# ProDoc_TwinWave_2026-01-06.net
KiCad netlist of a schematic drawn in EasyEDA Pro
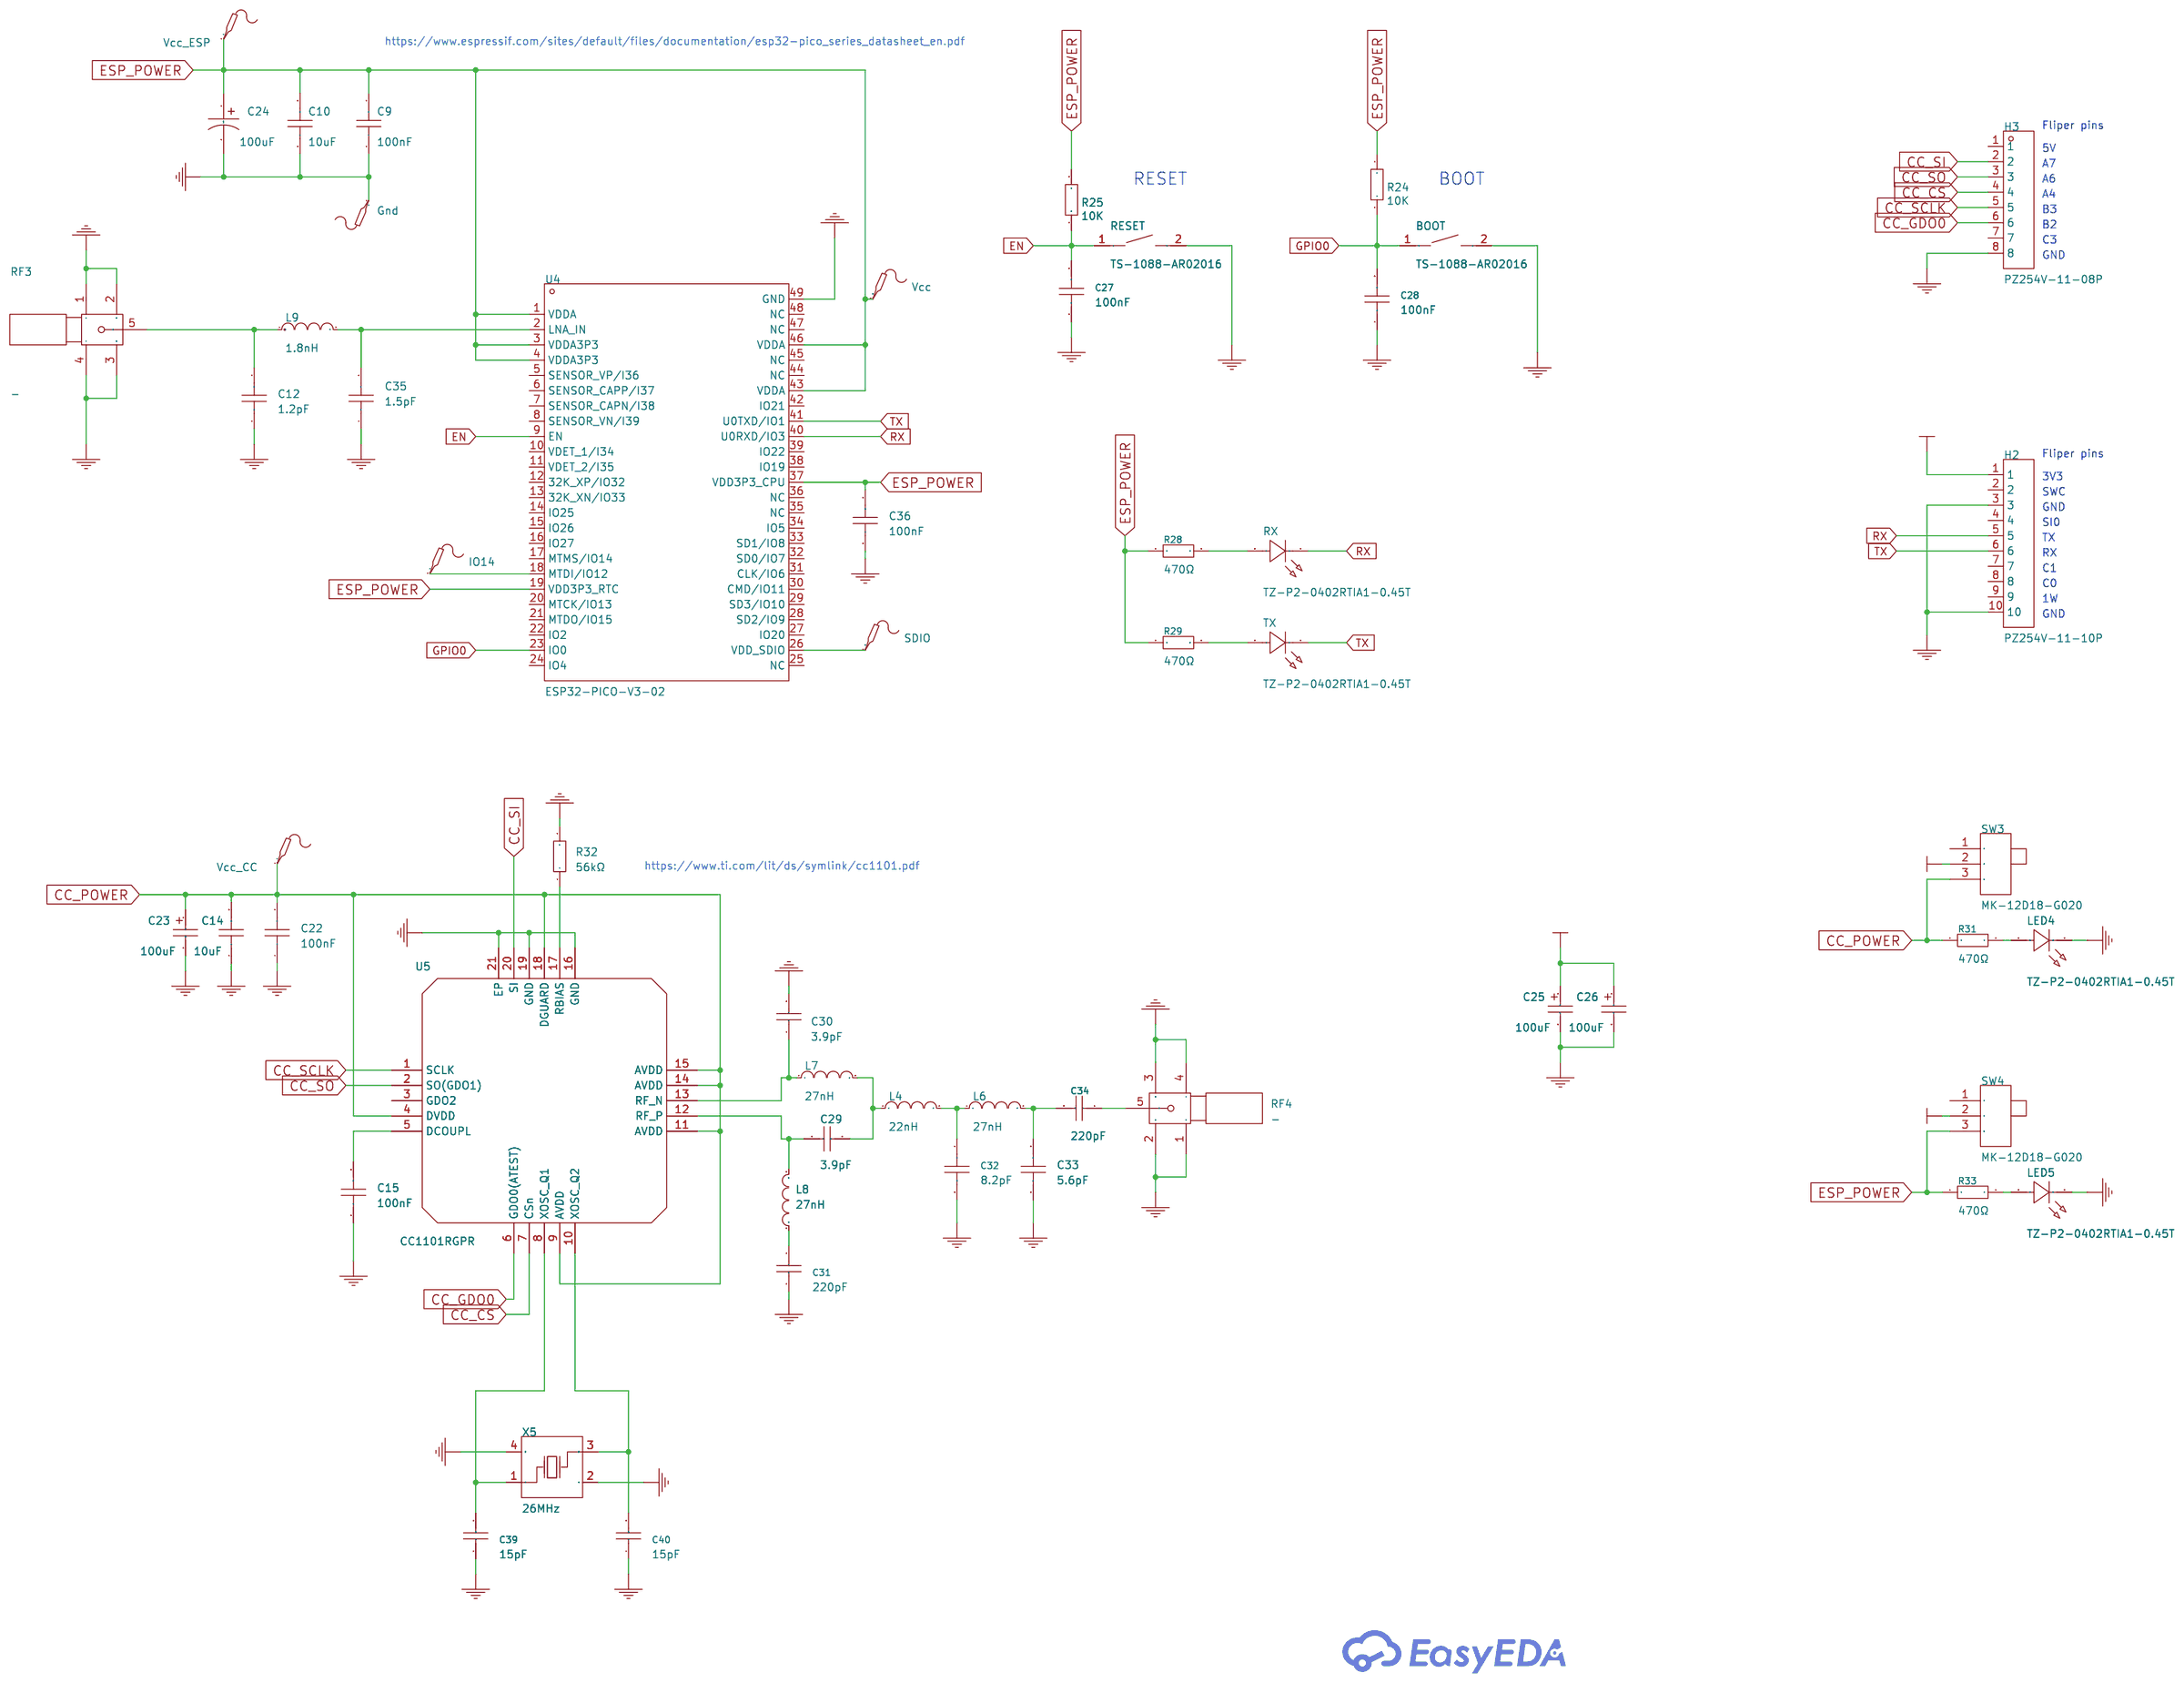
[diagram p0: schematic sheet]

(export (version "E")
  (design (tool "Eeschema 10.0.6"))
  (components
    (comp (ref "BOOT")
      (value "TS-1088-AR02016")
      (footprint "easyedapro:SW-SMD_L3.9-W3.0-P4.45")
      (fields (field (name "Manufacturer") "XUNPU(讯普)"))
      (libsource (lib "easyedapro") (part "TS-1088-AR02016"))
    )
    (comp (ref "C9")
      (value "100nF")
      (footprint "easyedapro:C0603")
      (description "Capacitance:100nF Tolerance:±10% Tolerance:±10% Voltage Rating:50V Temperature Coefficient:X7R")
      (fields
        (field (name "Manufacturer Part") "CC0603KRX7R9BB104")
        (field (name "Manufacturer") "YAGEO(国巨)")
      )
      (libsource (lib "easyedapro") (part "CC0603KRX7R9BB104"))
    )
    (comp (ref "C10")
      (value "10uF")
      (footprint "easyedapro:C0603")
      (fields
        (field (name "Manufacturer Part") "CL10A106MP8NNNC")
        (field (name "Manufacturer") "SAMSUNG(三星)")
      )
      (libsource (lib "easyedapro") (part "CL10A106MP8NNNC"))
    )
    (comp (ref "C12")
      (value "1.2pF")
      (footprint "easyedapro:C0201")
      (fields
        (field (name "Manufacturer Part") "GRM0335C1H1R2BA01D")
        (field (name "Manufacturer") "muRata(村田)")
      )
      (libsource (lib "easyedapro") (part "GRM0335C1H1R2BA01D"))
    )
    (comp (ref "C14")
      (value "10uF")
      (footprint "easyedapro:C0603")
      (fields
        (field (name "Manufacturer Part") "CL10A106MP8NNNC")
        (field (name "Manufacturer") "SAMSUNG(三星)")
      )
      (libsource (lib "easyedapro") (part "CL10A106MP8NNNC"))
    )
    (comp (ref "C15")
      (value "100nF")
      (footprint "easyedapro:C0603")
      (description "Capacitance:100nF Tolerance:±10% Tolerance:±10% Voltage Rating:50V Temperature Coefficient:X7R")
      (fields
        (field (name "Manufacturer Part") "CC0603KRX7R9BB104")
        (field (name "Manufacturer") "YAGEO(国巨)")
      )
      (libsource (lib "easyedapro") (part "CC0603KRX7R9BB104"))
    )
    (comp (ref "C22")
      (value "100nF")
      (footprint "easyedapro:C0603")
      (description "Capacitance:100nF Tolerance:±10% Tolerance:±10% Voltage Rating:50V Temperature Coefficient:X7R")
      (fields
        (field (name "Manufacturer Part") "CC0603KRX7R9BB104")
        (field (name "Manufacturer") "YAGEO(国巨)")
      )
      (libsource (lib "easyedapro") (part "CC0603KRX7R9BB104"))
    )
    (comp (ref "C23")
      (value "100uF")
      (footprint "easyedapro:CASE-B_3528")
      (fields (field (name "Manufacturer Part") "TAJB107K006RNJ") (field (name "Manufacturer") "Kyocera AVX"))
      (libsource (lib "easyedapro") (part "TAJB107K006RNJ"))
    )
    (comp (ref "C24")
      (value "100uF")
      (footprint "easyedapro:CASE-B_3528-1")
      (fields
        (field (name "Manufacturer Part") "TPSB107K006R0250")
        (field (name "Manufacturer") "Kyocera AVX")
      )
      (libsource (lib "easyedapro") (part "TPSB107K006R0250"))
    )
    (comp (ref "C25")
      (value "100uF")
      (footprint "easyedapro:CASE-B_3528")
      (fields (field (name "Manufacturer Part") "TAJB107K006RNJ") (field (name "Manufacturer") "Kyocera AVX"))
      (libsource (lib "easyedapro") (part "TAJB107K006RNJ"))
    )
    (comp (ref "C26")
      (value "100uF")
      (footprint "easyedapro:CASE-B_3528")
      (fields (field (name "Manufacturer Part") "TAJB107K006RNJ") (field (name "Manufacturer") "Kyocera AVX"))
      (libsource (lib "easyedapro") (part "TAJB107K006RNJ"))
    )
    (comp (ref "C27")
      (value "100nF")
      (footprint "easyedapro:C0402")
      (fields
        (field (name "Manufacturer Part") "CC0402KRX7R7BB104")
        (field (name "Manufacturer") "YAGEO(国巨)")
      )
      (libsource (lib "easyedapro") (part "CC0402KRX7R7BB104"))
    )
    (comp (ref "C28")
      (value "100nF")
      (footprint "easyedapro:C0402")
      (fields
        (field (name "Manufacturer Part") "CC0402KRX7R7BB104")
        (field (name "Manufacturer") "YAGEO(国巨)")
      )
      (libsource (lib "easyedapro") (part "CC0402KRX7R7BB104"))
    )
    (comp (ref "C29")
      (value "3.9pF")
      (footprint "easyedapro:C0402")
      (fields (field (name "Manufacturer Part") "0402CG3R9C500NT") (field (name "Manufacturer") "FH(风华)"))
      (libsource (lib "easyedapro") (part "0402CG3R9C500NT"))
    )
    (comp (ref "C30")
      (value "3.9pF")
      (footprint "easyedapro:C0402")
      (fields (field (name "Manufacturer Part") "0402CG3R9C500NT") (field (name "Manufacturer") "FH(风华)"))
      (libsource (lib "easyedapro") (part "0402CG3R9C500NT"))
    )
    (comp (ref "C31")
      (value "220pF")
      (footprint "easyedapro:C0402")
      (description "Capacitance:220pF Tolerance:±5% Tolerance:±5% Voltage Rating:50V Temperature Coefficient:NP0")
      (fields
        (field (name "Manufacturer Part") "CC0402JRNPO9BN221")
        (field (name "Manufacturer") "YAGEO(国巨)")
      )
      (libsource (lib "easyedapro") (part "CC0402JRNPO9BN221"))
    )
    (comp (ref "C32")
      (value "8.2pF")
      (footprint "easyedapro:C0402")
      (fields
        (field (name "Manufacturer Part") "CC0402BRNPO9BN8R2")
        (field (name "Manufacturer") "YAGEO(国巨)")
      )
      (libsource (lib "easyedapro") (part "CC0402BRNPO9BN8R2"))
    )
    (comp (ref "C33")
      (value "5.6pF")
      (footprint "easyedapro:C0402")
      (fields
        (field (name "Manufacturer Part") "CC0402BRNPO9BN5R6")
        (field (name "Manufacturer") "YAGEO(国巨)")
      )
      (libsource (lib "easyedapro") (part "CC0402BRNPO9BN5R6"))
    )
    (comp (ref "C34")
      (value "220pF")
      (footprint "easyedapro:C0402")
      (description "Capacitance:220pF Tolerance:±5% Tolerance:±5% Voltage Rating:50V Temperature Coefficient:NP0")
      (fields
        (field (name "Manufacturer Part") "CC0402JRNPO9BN221")
        (field (name "Manufacturer") "YAGEO(国巨)")
      )
      (libsource (lib "easyedapro") (part "CC0402JRNPO9BN221"))
    )
    (comp (ref "C35")
      (value "1.5pF")
      (footprint "easyedapro:C0201")
      (fields
        (field (name "Manufacturer Part") "GRM0335C1H1R5BA01D")
        (field (name "Manufacturer") "muRata(村田)")
      )
      (libsource (lib "easyedapro") (part "GRM0335C1H1R5BA01D"))
    )
    (comp (ref "C36")
      (value "100nF")
      (footprint "easyedapro:C0603")
      (description "Capacitance:100nF Tolerance:±10% Tolerance:±10% Voltage Rating:50V Temperature Coefficient:X7R")
      (fields
        (field (name "Manufacturer Part") "CC0603KRX7R9BB104")
        (field (name "Manufacturer") "YAGEO(国巨)")
      )
      (libsource (lib "easyedapro") (part "CC0603KRX7R9BB104"))
    )
    (comp (ref "C39")
      (value "15pF")
      (footprint "easyedapro:C0402")
      (fields
        (field (name "Manufacturer Part") "CC0402JRNPO9BN150")
        (field (name "Manufacturer") "YAGEO(国巨)")
      )
      (libsource (lib "easyedapro") (part "CC0402JRNPO9BN150"))
    )
    (comp (ref "C40")
      (value "15pF")
      (footprint "easyedapro:C0402")
      (fields
        (field (name "Manufacturer Part") "CC0402JRNPO9BN150")
        (field (name "Manufacturer") "YAGEO(国巨)")
      )
      (libsource (lib "easyedapro") (part "CC0402JRNPO9BN150"))
    )
    (comp (ref "Gnd")
      (value "~")
      (footprint "easyedapro:Test-Point-0.5mm")
      (description "Test Point 测试点")
      (libsource (lib "easyedapro") (part "Test-Point"))
    )
    (comp (ref "H2")
      (value "PZ254V-11-10P")
      (footprint "easyedapro:HDR-TH_10P-P2.54-V-M")
      (fields (field (name "Manufacturer") "XFCN(兴飞)"))
      (libsource (lib "easyedapro") (part "PZ254V-11-10P"))
    )
    (comp (ref "H3")
      (value "PZ254V-11-08P")
      (footprint "easyedapro:HDR-TH_8P-P2.54-V-M")
      (fields (field (name "Manufacturer") "XFCN(兴飞)"))
      (libsource (lib "easyedapro") (part "PZ254V-11-08P"))
    )
    (comp (ref "IO14")
      (value "~")
      (footprint "easyedapro:Test-Point-0.5mm")
      (description "Test Point 测试点")
      (libsource (lib "easyedapro") (part "Test-Point"))
    )
    (comp (ref "L4")
      (value "22nH")
      (footprint "easyedapro:L0402")
      (fields (field (name "Manufacturer Part") "LQG15HS22NJ02D") (field (name "Manufacturer") "muRata(村田)"))
      (libsource (lib "easyedapro") (part "LQG15HS22NJ02D"))
    )
    (comp (ref "L6")
      (value "27nH")
      (footprint "easyedapro:L0402-RD")
      (fields (field (name "Manufacturer Part") "LQG15HS27NJ02D") (field (name "Manufacturer") "muRata(村田)"))
      (libsource (lib "easyedapro") (part "LQG15HS27NJ02D"))
    )
    (comp (ref "L7")
      (value "27nH")
      (footprint "easyedapro:L0402-RD")
      (fields (field (name "Manufacturer Part") "LQG15HS27NJ02D") (field (name "Manufacturer") "muRata(村田)"))
      (libsource (lib "easyedapro") (part "LQG15HS27NJ02D"))
    )
    (comp (ref "L8")
      (value "27nH")
      (footprint "easyedapro:L0402-RD")
      (fields (field (name "Manufacturer Part") "LQG15HS27NJ02D") (field (name "Manufacturer") "muRata(村田)"))
      (libsource (lib "easyedapro") (part "LQG15HS27NJ02D"))
    )
    (comp (ref "L9")
      (value "1.8nH")
      (footprint "easyedapro:L0201-RD")
      (fields (field (name "Manufacturer Part") "LQP03TN1N8B02D") (field (name "Manufacturer") "muRata(村田)"))
      (libsource (lib "easyedapro") (part "LQP03TN1N8B02D"))
    )
    (comp (ref "LED4")
      (value "TZ-P2-0402RTIA1-0.45T")
      (footprint "easyedapro:LED0402-RD_RED")
      (fields (field (name "Manufacturer") "TUOZHAN(拓展光电)"))
      (libsource (lib "easyedapro") (part "TZ-P2-0402RTIA1-0.45T"))
    )
    (comp (ref "LED5")
      (value "TZ-P2-0402RTIA1-0.45T")
      (footprint "easyedapro:LED0402-RD_RED")
      (fields (field (name "Manufacturer") "TUOZHAN(拓展光电)"))
      (libsource (lib "easyedapro") (part "TZ-P2-0402RTIA1-0.45T"))
    )
    (comp (ref "R24")
      (value "10K")
      (footprint "easyedapro:R0603")
      (fields (field (name "Manufacturer Part") "RC0603DR-0710KL") (field (name "Manufacturer") "YAGEO(国巨)"))
      (libsource (lib "easyedapro") (part "10K"))
    )
    (comp (ref "R25")
      (value "10K")
      (footprint "easyedapro:R0603")
      (fields (field (name "Manufacturer Part") "RC0603DR-0710KL") (field (name "Manufacturer") "YAGEO(国巨)"))
      (libsource (lib "easyedapro") (part "10K"))
    )
    (comp (ref "R28")
      (value "470Ω")
      (footprint "easyedapro:R0402")
      (fields
        (field (name "Manufacturer Part") "0402WGF4700TCE")
        (field (name "Manufacturer") "UNI-ROYAL(厚声)")
      )
      (libsource (lib "easyedapro") (part "0402WGF4700TCE"))
    )
    (comp (ref "R29")
      (value "470Ω")
      (footprint "easyedapro:R0402")
      (fields
        (field (name "Manufacturer Part") "0402WGF4700TCE")
        (field (name "Manufacturer") "UNI-ROYAL(厚声)")
      )
      (libsource (lib "easyedapro") (part "0402WGF4700TCE"))
    )
    (comp (ref "R31")
      (value "470Ω")
      (footprint "easyedapro:R0402")
      (fields
        (field (name "Manufacturer Part") "0402WGF4700TCE")
        (field (name "Manufacturer") "UNI-ROYAL(厚声)")
      )
      (libsource (lib "easyedapro") (part "0402WGF4700TCE"))
    )
    (comp (ref "R32")
      (value "56kΩ")
      (footprint "easyedapro:R0402")
      (fields
        (field (name "Manufacturer Part") "0402WGF5602TCE")
        (field (name "Manufacturer") "UNI-ROYAL(厚声)")
      )
      (libsource (lib "easyedapro") (part "0402WGF5602TCE"))
    )
    (comp (ref "R33")
      (value "470Ω")
      (footprint "easyedapro:R0402")
      (fields
        (field (name "Manufacturer Part") "0402WGF4700TCE")
        (field (name "Manufacturer") "UNI-ROYAL(厚声)")
      )
      (libsource (lib "easyedapro") (part "0402WGF4700TCE"))
    )
    (comp (ref "RESET")
      (value "TS-1088-AR02016")
      (footprint "easyedapro:SW-SMD_L3.9-W3.0-P4.45")
      (fields (field (name "Manufacturer") "XUNPU(讯普)"))
      (libsource (lib "easyedapro") (part "TS-1088-AR02016"))
    )
    (comp (ref "RF3")
      (value "-")
      (footprint "easyedapro:SMA-SMD_BWSMA-KE-P001")
      (fields
        (field (name "Manufacturer Part") "BWSMA-KE-P001")
        (field (name "Manufacturer") "BAT WIRELESS(蝙蝠无线)")
      )
      (libsource (lib "easyedapro") (part "BWSMA-KE-P001"))
    )
    (comp (ref "RF4")
      (value "-")
      (footprint "easyedapro:SMA-SMD_BWSMA-KE-P001")
      (fields
        (field (name "Manufacturer Part") "BWSMA-KE-P001")
        (field (name "Manufacturer") "BAT WIRELESS(蝙蝠无线)")
      )
      (libsource (lib "easyedapro") (part "BWSMA-KE-P001"))
    )
    (comp (ref "RX")
      (value "TZ-P2-0402RTIA1-0.45T")
      (footprint "easyedapro:LED0402-RD_RED")
      (fields (field (name "Manufacturer") "TUOZHAN(拓展光电)"))
      (libsource (lib "easyedapro") (part "TZ-P2-0402RTIA1-0.45T"))
    )
    (comp (ref "SDIO")
      (value "~")
      (footprint "easyedapro:Test-Point-0.5mm")
      (description "Test Point 测试点")
      (libsource (lib "easyedapro") (part "Test-Point"))
    )
    (comp (ref "SW3")
      (value "MK-12D18-G020")
      (footprint "easyedapro:SW-TH_MK-12D18-G040")
      (fields (field (name "Manufacturer") "G-Switch(品赞)"))
      (libsource (lib "easyedapro") (part "MK-12D18-G020"))
    )
    (comp (ref "SW4")
      (value "MK-12D18-G020")
      (footprint "easyedapro:SW-TH_MK-12D18-G040")
      (fields (field (name "Manufacturer") "G-Switch(品赞)"))
      (libsource (lib "easyedapro") (part "MK-12D18-G020"))
    )
    (comp (ref "TX")
      (value "TZ-P2-0402RTIA1-0.45T")
      (footprint "easyedapro:LED0402-RD_RED")
      (fields (field (name "Manufacturer") "TUOZHAN(拓展光电)"))
      (libsource (lib "easyedapro") (part "TZ-P2-0402RTIA1-0.45T"))
    )
    (comp (ref "U4")
      (value "ESP32-PICO-V3-02")
      (footprint "easyedapro:QFN-48_L7.0-W7.0-P0.50-BL-EP5.1")
      (fields (field (name "Manufacturer") "ESPRESSIF(乐鑫)"))
      (libsource (lib "easyedapro") (part "ESP32-PICO-V3-02"))
    )
    (comp (ref "U5")
      (value "CC1101RGPR")
      (footprint "easyedapro:QFN-20_L4.0-W4.0-P0.5-TL-EP")
      (fields (field (name "Manufacturer") "TI(德州仪器)"))
      (libsource (lib "easyedapro") (part "CC1101RGPR"))
    )
    (comp (ref "Vcc")
      (value "~")
      (footprint "easyedapro:Test-Point-0.5mm")
      (description "Test Point 测试点")
      (libsource (lib "easyedapro") (part "Test-Point"))
    )
    (comp (ref "Vcc_CC")
      (value "~")
      (footprint "easyedapro:Test-Point-0.5mm")
      (description "Test Point 测试点")
      (libsource (lib "easyedapro") (part "Test-Point"))
    )
    (comp (ref "Vcc_ESP")
      (value "~")
      (footprint "easyedapro:Test-Point-0.5mm")
      (description "Test Point 测试点")
      (libsource (lib "easyedapro") (part "Test-Point"))
    )
    (comp (ref "X5")
      (value "26MHz")
      (footprint "easyedapro:CRYSTAL-SMD_4P-L3.2-W2.5-BL")
      (fields (field (name "Manufacturer Part") "X322526MMB4SI") (field (name "Manufacturer") "YXC(扬兴晶振)"))
      (libsource (lib "easyedapro") (part "X322526MMB4SI"))
    )
  )
  (nets
    (net (code "1") (name "3V3") (class "Default")
      (node (ref "C25") (pin "1") (pinfunction "1_1") (pintype "input"))
      (node (ref "C26") (pin "1") (pinfunction "1_1") (pintype "input"))
      (node (ref "H2") (pin "1") (pinfunction "1_1") (pintype "unspecified"))
      (node (ref "SW3") (pin "2") (pinfunction "2_2") (pintype "unspecified"))
      (node (ref "SW4") (pin "2") (pinfunction "2_2") (pintype "unspecified"))
    )
    (net (code "2") (name "CC_CS") (class "Default")
      (node (ref "H3") (pin "4") (pinfunction "4_4") (pintype "unspecified"))
      (node (ref "U5") (pin "7") (pinfunction "CSn_7") (pintype "unspecified"))
    )
    (net (code "3") (name "CC_GDO0") (class "Default")
      (node (ref "H3") (pin "6") (pinfunction "6_6") (pintype "unspecified"))
      (node (ref "U5") (pin "6") (pinfunction "GDO0(ATEST)_6") (pintype "unspecified"))
    )
    (net (code "4") (name "CC_POWER") (class "Default")
      (node (ref "C14") (pin "2") (pinfunction "2_2") (pintype "unspecified"))
      (node (ref "C22") (pin "2") (pinfunction "2_2") (pintype "unspecified"))
      (node (ref "C23") (pin "1") (pinfunction "1_1") (pintype "input"))
      (node (ref "R31") (pin "1") (pinfunction "1_1") (pintype "input"))
      (node (ref "SW3") (pin "3") (pinfunction "3_3") (pintype "unspecified"))
      (node (ref "U5") (pin "11") (pinfunction "AVDD_11") (pintype "unspecified"))
      (node (ref "U5") (pin "14") (pinfunction "AVDD_14") (pintype "unspecified"))
      (node (ref "U5") (pin "15") (pinfunction "AVDD_15") (pintype "unspecified"))
      (node (ref "U5") (pin "18") (pinfunction "DGUARD_18") (pintype "unspecified"))
      (node (ref "U5") (pin "4") (pinfunction "DVDD_4") (pintype "unspecified"))
      (node (ref "U5") (pin "9") (pinfunction "AVDD_9") (pintype "unspecified"))
      (node (ref "Vcc_CC") (pin "1") (pinfunction "1_1") (pintype "unspecified"))
    )
    (net (code "5") (name "CC_SCLK") (class "Default")
      (node (ref "H3") (pin "5") (pinfunction "5_5") (pintype "unspecified"))
      (node (ref "U5") (pin "1") (pinfunction "SCLK_1") (pintype "unspecified"))
    )
    (net (code "6") (name "CC_SI") (class "Default")
      (node (ref "H3") (pin "2") (pinfunction "2_2") (pintype "unspecified"))
      (node (ref "U5") (pin "20") (pinfunction "SI_20") (pintype "unspecified"))
    )
    (net (code "7") (name "CC_SO") (class "Default")
      (node (ref "H3") (pin "3") (pinfunction "3_3") (pintype "unspecified"))
      (node (ref "U5") (pin "2") (pinfunction "SO(GDO1)_2") (pintype "unspecified"))
    )
    (net (code "8") (name "EN") (class "Default")
      (node (ref "C27") (pin "2") (pinfunction "2_2") (pintype "input"))
      (node (ref "R25") (pin "1") (pinfunction "1_1") (pintype "input"))
      (node (ref "RESET") (pin "1") (pinfunction "1_1") (pintype "unspecified"))
      (node (ref "U4") (pin "9") (pinfunction "EN_9") (pintype "unspecified"))
    )
    (net (code "9") (name "ESP_POWER") (class "Default")
      (node (ref "C10") (pin "2") (pinfunction "2_2") (pintype "unspecified"))
      (node (ref "C24") (pin "1") (pinfunction "1_1") (pintype "unspecified"))
      (node (ref "C36") (pin "2") (pinfunction "2_2") (pintype "unspecified"))
      (node (ref "C9") (pin "2") (pinfunction "2_2") (pintype "unspecified"))
      (node (ref "R24") (pin "2") (pinfunction "2_2") (pintype "input"))
      (node (ref "R25") (pin "2") (pinfunction "2_2") (pintype "input"))
      (node (ref "R28") (pin "1") (pinfunction "1_1") (pintype "input"))
      (node (ref "R29") (pin "1") (pinfunction "1_1") (pintype "input"))
      (node (ref "R33") (pin "1") (pinfunction "1_1") (pintype "input"))
      (node (ref "SW4") (pin "3") (pinfunction "3_3") (pintype "unspecified"))
      (node (ref "U4") (pin "1") (pinfunction "VDDA_1") (pintype "unspecified"))
      (node (ref "U4") (pin "19") (pinfunction "VDD3P3_RTC_19") (pintype "unspecified"))
      (node (ref "U4") (pin "3") (pinfunction "VDDA3P3_3") (pintype "unspecified"))
      (node (ref "U4") (pin "37") (pinfunction "VDD3P3_CPU_37") (pintype "unspecified"))
      (node (ref "U4") (pin "4") (pinfunction "VDDA3P3_4") (pintype "unspecified"))
      (node (ref "U4") (pin "43") (pinfunction "VDDA_43") (pintype "unspecified"))
      (node (ref "U4") (pin "46") (pinfunction "VDDA_46") (pintype "unspecified"))
      (node (ref "Vcc") (pin "1") (pinfunction "1_1") (pintype "unspecified"))
      (node (ref "Vcc_ESP") (pin "1") (pinfunction "1_1") (pintype "unspecified"))
    )
    (net (code "10") (name "GND") (class "Default")
      (node (ref "BOOT") (pin "2") (pinfunction "2_2") (pintype "unspecified"))
      (node (ref "C10") (pin "1") (pinfunction "1_1") (pintype "unspecified"))
      (node (ref "C12") (pin "1") (pinfunction "1_1") (pintype "unspecified"))
      (node (ref "C14") (pin "1") (pinfunction "1_1") (pintype "unspecified"))
      (node (ref "C15") (pin "1") (pinfunction "1_1") (pintype "unspecified"))
      (node (ref "C22") (pin "1") (pinfunction "1_1") (pintype "unspecified"))
      (node (ref "C23") (pin "2") (pinfunction "2_2") (pintype "input"))
      (node (ref "C24") (pin "2") (pinfunction "2_2") (pintype "unspecified"))
      (node (ref "C25") (pin "2") (pinfunction "2_2") (pintype "input"))
      (node (ref "C26") (pin "2") (pinfunction "2_2") (pintype "input"))
      (node (ref "C27") (pin "1") (pinfunction "1_1") (pintype "input"))
      (node (ref "C28") (pin "1") (pinfunction "1_1") (pintype "input"))
      (node (ref "C30") (pin "2") (pinfunction "2_2") (pintype "input"))
      (node (ref "C31") (pin "1") (pinfunction "1_1") (pintype "input"))
      (node (ref "C32") (pin "2") (pinfunction "2_2") (pintype "input"))
      (node (ref "C33") (pin "1") (pinfunction "1_1") (pintype "unspecified"))
      (node (ref "C35") (pin "1") (pinfunction "1_1") (pintype "unspecified"))
      (node (ref "C36") (pin "1") (pinfunction "1_1") (pintype "unspecified"))
      (node (ref "C39") (pin "1") (pinfunction "1_1") (pintype "input"))
      (node (ref "C40") (pin "1") (pinfunction "1_1") (pintype "input"))
      (node (ref "C9") (pin "1") (pinfunction "1_1") (pintype "unspecified"))
      (node (ref "Gnd") (pin "1") (pinfunction "1_1") (pintype "unspecified"))
      (node (ref "H2") (pin "10") (pinfunction "10_10") (pintype "unspecified"))
      (node (ref "H2") (pin "3") (pinfunction "3_3") (pintype "unspecified"))
      (node (ref "H3") (pin "8") (pinfunction "8_8") (pintype "unspecified"))
      (node (ref "LED4") (pin "1") (pinfunction "K_1") (pintype "unspecified"))
      (node (ref "LED5") (pin "1") (pinfunction "K_1") (pintype "unspecified"))
      (node (ref "R32") (pin "2") (pinfunction "2_2") (pintype "input"))
      (node (ref "RESET") (pin "2") (pinfunction "2_2") (pintype "unspecified"))
      (node (ref "RF3") (pin "1") (pinfunction "1_1") (pintype "unspecified"))
      (node (ref "RF3") (pin "2") (pinfunction "2_2") (pintype "unspecified"))
      (node (ref "RF3") (pin "3") (pinfunction "3_3") (pintype "unspecified"))
      (node (ref "RF3") (pin "4") (pinfunction "4_4") (pintype "unspecified"))
      (node (ref "RF4") (pin "1") (pinfunction "1_1") (pintype "unspecified"))
      (node (ref "RF4") (pin "2") (pinfunction "2_2") (pintype "unspecified"))
      (node (ref "RF4") (pin "3") (pinfunction "3_3") (pintype "unspecified"))
      (node (ref "RF4") (pin "4") (pinfunction "4_4") (pintype "unspecified"))
      (node (ref "U4") (pin "49") (pinfunction "GND_49") (pintype "unspecified"))
      (node (ref "U5") (pin "16") (pinfunction "GND_16") (pintype "unspecified"))
      (node (ref "U5") (pin "19") (pinfunction "GND_19") (pintype "unspecified"))
      (node (ref "U5") (pin "21") (pinfunction "EP_21") (pintype "unspecified"))
      (node (ref "X5") (pin "2") (pinfunction "GND_2") (pintype "unspecified"))
      (node (ref "X5") (pin "4") (pinfunction "GND_4") (pintype "unspecified"))
    )
    (net (code "11") (name "GPIO0") (class "Default")
      (node (ref "BOOT") (pin "1") (pinfunction "1_1") (pintype "unspecified"))
      (node (ref "C28") (pin "2") (pinfunction "2_2") (pintype "input"))
      (node (ref "R24") (pin "1") (pinfunction "1_1") (pintype "input"))
      (node (ref "U4") (pin "23") (pinfunction "IO0_23") (pintype "unspecified"))
    )
    (net (code "12") (name "Net-(C12-Pad2)") (class "Default")
      (node (ref "C12") (pin "2") (pinfunction "2_2") (pintype "unspecified"))
      (node (ref "L9") (pin "1") (pinfunction "1_1") (pintype "input"))
      (node (ref "RF3") (pin "5") (pinfunction "5_5") (pintype "unspecified"))
    )
    (net (code "13") (name "Net-(C29-Pad2)") (class "Default")
      (node (ref "C29") (pin "2") (pinfunction "2_2") (pintype "input"))
      (node (ref "L4") (pin "1") (pinfunction "1_1") (pintype "unspecified"))
      (node (ref "L7") (pin "2") (pinfunction "2_2") (pintype "unspecified"))
    )
    (net (code "14") (name "Net-(C31-Pad2)") (class "Default")
      (node (ref "C31") (pin "2") (pinfunction "2_2") (pintype "input"))
      (node (ref "L8") (pin "1") (pinfunction "1_1") (pintype "unspecified"))
    )
    (net (code "15") (name "Net-(C32-Pad1)") (class "Default")
      (node (ref "C32") (pin "1") (pinfunction "1_1") (pintype "input"))
      (node (ref "L4") (pin "2") (pinfunction "2_2") (pintype "unspecified"))
      (node (ref "L6") (pin "1") (pinfunction "1_1") (pintype "unspecified"))
    )
    (net (code "16") (name "Net-(C33-Pad2)") (class "Default")
      (node (ref "C33") (pin "2") (pinfunction "2_2") (pintype "unspecified"))
      (node (ref "C34") (pin "2") (pinfunction "2_2") (pintype "input"))
      (node (ref "L6") (pin "2") (pinfunction "2_2") (pintype "unspecified"))
    )
    (net (code "17") (name "Net-(C34-Pad1)") (class "Default")
      (node (ref "C34") (pin "1") (pinfunction "1_1") (pintype "input"))
      (node (ref "RF4") (pin "5") (pinfunction "5_5") (pintype "unspecified"))
    )
    (net (code "18") (name "Net-(LED4-A)") (class "Default")
      (node (ref "LED4") (pin "2") (pinfunction "A_2") (pintype "unspecified"))
      (node (ref "R31") (pin "2") (pinfunction "2_2") (pintype "input"))
    )
    (net (code "19") (name "Net-(LED5-A)") (class "Default")
      (node (ref "LED5") (pin "2") (pinfunction "A_2") (pintype "unspecified"))
      (node (ref "R33") (pin "2") (pinfunction "2_2") (pintype "input"))
    )
    (net (code "20") (name "Net-(RX-A)") (class "Default")
      (node (ref "R28") (pin "2") (pinfunction "2_2") (pintype "input"))
      (node (ref "RX") (pin "2") (pinfunction "A_2") (pintype "unspecified"))
    )
    (net (code "21") (name "Net-(TX-A)") (class "Default")
      (node (ref "R29") (pin "2") (pinfunction "2_2") (pintype "input"))
      (node (ref "TX") (pin "2") (pinfunction "A_2") (pintype "unspecified"))
    )
    (net (code "22") (name "Net-(U4-LNA_IN)") (class "Default")
      (node (ref "C35") (pin "2") (pinfunction "2_2") (pintype "unspecified"))
      (node (ref "L9") (pin "2") (pinfunction "2_2") (pintype "input"))
      (node (ref "U4") (pin "2") (pinfunction "LNA_IN_2") (pintype "unspecified"))
    )
    (net (code "23") (name "Net-(U4-MTDI{slash}IO12)") (class "Default")
      (node (ref "IO14") (pin "1") (pinfunction "1_1") (pintype "unspecified"))
      (node (ref "U4") (pin "18") (pinfunction "MTDI/IO12_18") (pintype "unspecified"))
    )
    (net (code "24") (name "Net-(U4-VDD_SDIO)") (class "Default")
      (node (ref "SDIO") (pin "1") (pinfunction "1_1") (pintype "unspecified"))
      (node (ref "U4") (pin "26") (pinfunction "VDD_SDIO_26") (pintype "unspecified"))
    )
    (net (code "25") (name "Net-(U5-DCOUPL)") (class "Default")
      (node (ref "C15") (pin "2") (pinfunction "2_2") (pintype "unspecified"))
      (node (ref "U5") (pin "5") (pinfunction "DCOUPL_5") (pintype "unspecified"))
    )
    (net (code "26") (name "Net-(U5-RBIAS)") (class "Default")
      (node (ref "R32") (pin "1") (pinfunction "1_1") (pintype "input"))
      (node (ref "U5") (pin "17") (pinfunction "RBIAS_17") (pintype "unspecified"))
    )
    (net (code "27") (name "Net-(U5-RF_N)") (class "Default")
      (node (ref "C30") (pin "1") (pinfunction "1_1") (pintype "input"))
      (node (ref "L7") (pin "1") (pinfunction "1_1") (pintype "unspecified"))
      (node (ref "U5") (pin "13") (pinfunction "RF_N_13") (pintype "unspecified"))
    )
    (net (code "28") (name "Net-(U5-RF_P)") (class "Default")
      (node (ref "C29") (pin "1") (pinfunction "1_1") (pintype "input"))
      (node (ref "L8") (pin "2") (pinfunction "2_2") (pintype "unspecified"))
      (node (ref "U5") (pin "12") (pinfunction "RF_P_12") (pintype "unspecified"))
    )
    (net (code "29") (name "Net-(U5-XOSC_Q1)") (class "Default")
      (node (ref "C39") (pin "2") (pinfunction "2_2") (pintype "input"))
      (node (ref "U5") (pin "8") (pinfunction "XOSC_Q1_8") (pintype "unspecified"))
      (node (ref "X5") (pin "1") (pinfunction "OSC1_1") (pintype "unspecified"))
    )
    (net (code "30") (name "Net-(U5-XOSC_Q2)") (class "Default")
      (node (ref "C40") (pin "2") (pinfunction "2_2") (pintype "input"))
      (node (ref "U5") (pin "10") (pinfunction "XOSC_Q2_10") (pintype "unspecified"))
      (node (ref "X5") (pin "3") (pinfunction "OSC2_3") (pintype "unspecified"))
    )
    (net (code "31") (name "RX") (class "Default")
      (node (ref "H2") (pin "5") (pinfunction "5_5") (pintype "unspecified"))
      (node (ref "RX") (pin "1") (pinfunction "K_1") (pintype "unspecified"))
      (node (ref "U4") (pin "40") (pinfunction "U0RXD/IO3_40") (pintype "unspecified"))
    )
    (net (code "32") (name "TX") (class "Default")
      (node (ref "H2") (pin "6") (pinfunction "6_6") (pintype "unspecified"))
      (node (ref "TX") (pin "1") (pinfunction "K_1") (pintype "unspecified"))
      (node (ref "U4") (pin "41") (pinfunction "U0TXD/IO1_41") (pintype "unspecified"))
    )
    (net (code "33") (name "unconnected-(H2-Pad2)") (class "Default")
      (node (ref "H2") (pin "2") (pinfunction "2_2") (pintype "unspecified"))
    )
    (net (code "34") (name "unconnected-(H2-Pad4)") (class "Default")
      (node (ref "H2") (pin "4") (pinfunction "4_4") (pintype "unspecified"))
    )
    (net (code "35") (name "unconnected-(H2-Pad7)") (class "Default")
      (node (ref "H2") (pin "7") (pinfunction "7_7") (pintype "unspecified"))
    )
    (net (code "36") (name "unconnected-(H2-Pad8)") (class "Default")
      (node (ref "H2") (pin "8") (pinfunction "8_8") (pintype "unspecified"))
    )
    (net (code "37") (name "unconnected-(H2-Pad9)") (class "Default")
      (node (ref "H2") (pin "9") (pinfunction "9_9") (pintype "unspecified"))
    )
    (net (code "38") (name "unconnected-(H3-Pad1)") (class "Default")
      (node (ref "H3") (pin "1") (pinfunction "1_1") (pintype "unspecified"))
    )
    (net (code "39") (name "unconnected-(H3-Pad7)") (class "Default")
      (node (ref "H3") (pin "7") (pinfunction "7_7") (pintype "unspecified"))
    )
    (net (code "40") (name "unconnected-(SW3-Pad1)") (class "Default")
      (node (ref "SW3") (pin "1") (pinfunction "1_1") (pintype "unspecified"))
    )
    (net (code "41") (name "unconnected-(SW4-Pad1)") (class "Default")
      (node (ref "SW4") (pin "1") (pinfunction "1_1") (pintype "unspecified"))
    )
    (net (code "42") (name "unconnected-(U4-32K_XN{slash}IO33-Pad13)") (class "Default")
      (node (ref "U4") (pin "13") (pinfunction "32K_XN/IO33_13") (pintype "unspecified"))
    )
    (net (code "43") (name "unconnected-(U4-32K_XP{slash}IO32-Pad12)") (class "Default")
      (node (ref "U4") (pin "12") (pinfunction "32K_XP/IO32_12") (pintype "unspecified"))
    )
    (net (code "44") (name "unconnected-(U4-CLK{slash}IO6-Pad31)") (class "Default")
      (node (ref "U4") (pin "31") (pinfunction "CLK/IO6_31") (pintype "unspecified"))
    )
    (net (code "45") (name "unconnected-(U4-CMD{slash}IO11-Pad30)") (class "Default")
      (node (ref "U4") (pin "30") (pinfunction "CMD/IO11_30") (pintype "unspecified"))
    )
    (net (code "46") (name "unconnected-(U4-IO2-Pad22)") (class "Default")
      (node (ref "U4") (pin "22") (pinfunction "IO2_22") (pintype "unspecified"))
    )
    (net (code "47") (name "unconnected-(U4-IO4-Pad24)") (class "Default")
      (node (ref "U4") (pin "24") (pinfunction "IO4_24") (pintype "unspecified"))
    )
    (net (code "48") (name "unconnected-(U4-IO5-Pad34)") (class "Default")
      (node (ref "U4") (pin "34") (pinfunction "IO5_34") (pintype "unspecified"))
    )
    (net (code "49") (name "unconnected-(U4-IO19-Pad38)") (class "Default")
      (node (ref "U4") (pin "38") (pinfunction "IO19_38") (pintype "unspecified"))
    )
    (net (code "50") (name "unconnected-(U4-IO20-Pad27)") (class "Default")
      (node (ref "U4") (pin "27") (pinfunction "IO20_27") (pintype "unspecified"))
    )
    (net (code "51") (name "unconnected-(U4-IO21-Pad42)") (class "Default")
      (node (ref "U4") (pin "42") (pinfunction "IO21_42") (pintype "unspecified"))
    )
    (net (code "52") (name "unconnected-(U4-IO22-Pad39)") (class "Default")
      (node (ref "U4") (pin "39") (pinfunction "IO22_39") (pintype "unspecified"))
    )
    (net (code "53") (name "unconnected-(U4-IO25-Pad14)") (class "Default")
      (node (ref "U4") (pin "14") (pinfunction "IO25_14") (pintype "unspecified"))
    )
    (net (code "54") (name "unconnected-(U4-IO26-Pad15)") (class "Default")
      (node (ref "U4") (pin "15") (pinfunction "IO26_15") (pintype "unspecified"))
    )
    (net (code "55") (name "unconnected-(U4-IO27-Pad16)") (class "Default")
      (node (ref "U4") (pin "16") (pinfunction "IO27_16") (pintype "unspecified"))
    )
    (net (code "56") (name "unconnected-(U4-MTCK{slash}IO13-Pad20)") (class "Default")
      (node (ref "U4") (pin "20") (pinfunction "MTCK/IO13_20") (pintype "unspecified"))
    )
    (net (code "57") (name "unconnected-(U4-MTDO{slash}IO15-Pad21)") (class "Default")
      (node (ref "U4") (pin "21") (pinfunction "MTDO/IO15_21") (pintype "unspecified"))
    )
    (net (code "58") (name "unconnected-(U4-MTMS{slash}IO14-Pad17)") (class "Default")
      (node (ref "U4") (pin "17") (pinfunction "MTMS/IO14_17") (pintype "unspecified"))
    )
    (net (code "59") (name "unconnected-(U4-NC-Pad25)") (class "Default")
      (node (ref "U4") (pin "25") (pinfunction "NC_25") (pintype "unspecified"))
    )
    (net (code "60") (name "unconnected-(U4-NC-Pad35)") (class "Default")
      (node (ref "U4") (pin "35") (pinfunction "NC_35") (pintype "unspecified"))
    )
    (net (code "61") (name "unconnected-(U4-NC-Pad36)") (class "Default")
      (node (ref "U4") (pin "36") (pinfunction "NC_36") (pintype "unspecified"))
    )
    (net (code "62") (name "unconnected-(U4-NC-Pad44)") (class "Default")
      (node (ref "U4") (pin "44") (pinfunction "NC_44") (pintype "unspecified"))
    )
    (net (code "63") (name "unconnected-(U4-NC-Pad45)") (class "Default")
      (node (ref "U4") (pin "45") (pinfunction "NC_45") (pintype "unspecified"))
    )
    (net (code "64") (name "unconnected-(U4-NC-Pad47)") (class "Default")
      (node (ref "U4") (pin "47") (pinfunction "NC_47") (pintype "unspecified"))
    )
    (net (code "65") (name "unconnected-(U4-NC-Pad48)") (class "Default")
      (node (ref "U4") (pin "48") (pinfunction "NC_48") (pintype "unspecified"))
    )
    (net (code "66") (name "unconnected-(U4-SD0{slash}IO7-Pad32)") (class "Default")
      (node (ref "U4") (pin "32") (pinfunction "SD0/IO7_32") (pintype "unspecified"))
    )
    (net (code "67") (name "unconnected-(U4-SD1{slash}IO8-Pad33)") (class "Default")
      (node (ref "U4") (pin "33") (pinfunction "SD1/IO8_33") (pintype "unspecified"))
    )
    (net (code "68") (name "unconnected-(U4-SD2{slash}IO9-Pad28)") (class "Default")
      (node (ref "U4") (pin "28") (pinfunction "SD2/IO9_28") (pintype "unspecified"))
    )
    (net (code "69") (name "unconnected-(U4-SD3{slash}IO10-Pad29)") (class "Default")
      (node (ref "U4") (pin "29") (pinfunction "SD3/IO10_29") (pintype "unspecified"))
    )
    (net (code "70") (name "unconnected-(U4-SENSOR_CAPN{slash}I38-Pad7)") (class "Default")
      (node (ref "U4") (pin "7") (pinfunction "SENSOR_CAPN/I38_7") (pintype "unspecified"))
    )
    (net (code "71") (name "unconnected-(U4-SENSOR_CAPP{slash}I37-Pad6)") (class "Default")
      (node (ref "U4") (pin "6") (pinfunction "SENSOR_CAPP/I37_6") (pintype "unspecified"))
    )
    (net (code "72") (name "unconnected-(U4-SENSOR_VN{slash}I39-Pad8)") (class "Default")
      (node (ref "U4") (pin "8") (pinfunction "SENSOR_VN/I39_8") (pintype "unspecified"))
    )
    (net (code "73") (name "unconnected-(U4-SENSOR_VP{slash}I36-Pad5)") (class "Default")
      (node (ref "U4") (pin "5") (pinfunction "SENSOR_VP/I36_5") (pintype "unspecified"))
    )
    (net (code "74") (name "unconnected-(U4-VDET_1{slash}I34-Pad10)") (class "Default")
      (node (ref "U4") (pin "10") (pinfunction "VDET_1/I34_10") (pintype "unspecified"))
    )
    (net (code "75") (name "unconnected-(U4-VDET_2{slash}I35-Pad11)") (class "Default")
      (node (ref "U4") (pin "11") (pinfunction "VDET_2/I35_11") (pintype "unspecified"))
    )
    (net (code "76") (name "unconnected-(U5-GDO2-Pad3)") (class "Default")
      (node (ref "U5") (pin "3") (pinfunction "GDO2_3") (pintype "unspecified"))
    )
  )
)
